# ArdBir_final.net
KiCad netlist of a schematic drawn in EAGLE
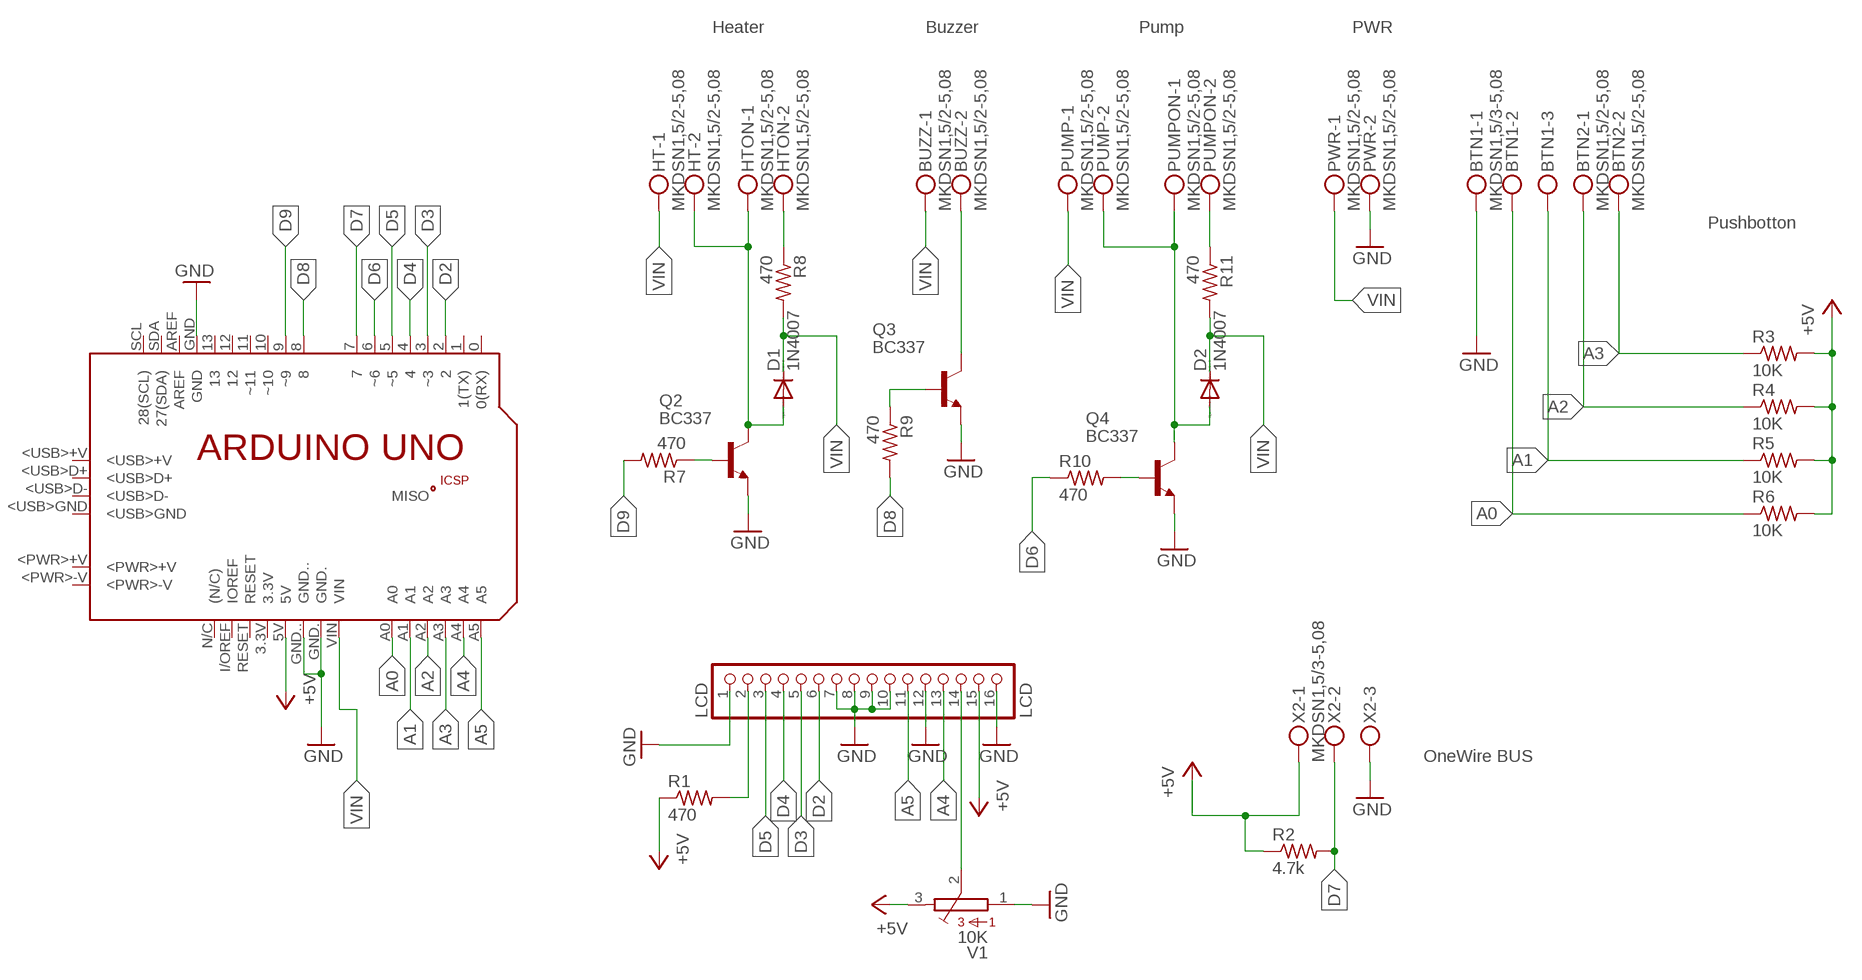
[diagram p0: schematic, sheet 1]

(export (version "E")
  (design (tool "Eeschema 10.0.6"))
  (components
    (comp (ref "BTN1")
      (value "MKDSN1,5/3-5,08")
      (footprint "eagle-import:MKDSN1,5_3-5,08")
      (fields (field (name "OC_NEWARK") "unknown"))
      (libsource (lib "eagle-import") (part "MKDSN1,5/3-5,08"))
    )
    (comp (ref "BTN2")
      (value "MKDSN1,5/2-5,08")
      (footprint "eagle-import:MKDSN1,5_2-5,08")
      (fields (field (name "OC_NEWARK") "unknown"))
      (libsource (lib "eagle-import") (part "MKDSN1,5/2-5,08"))
    )
    (comp (ref "BUZZ")
      (value "MKDSN1,5/2-5,08")
      (footprint "eagle-import:MKDSN1,5_2-5,08")
      (fields (field (name "OC_NEWARK") "unknown"))
      (libsource (lib "eagle-import") (part "MKDSN1,5/2-5,08"))
    )
    (comp (ref "D1")
      (value "1N4007")
      (footprint "eagle-import:DO41-10")
      (libsource (lib "eagle-import") (part "1N4004"))
    )
    (comp (ref "D2")
      (value "1N4007")
      (footprint "eagle-import:DO41-10")
      (libsource (lib "eagle-import") (part "1N4004"))
    )
    (comp (ref "HT")
      (value "MKDSN1,5/2-5,08")
      (footprint "eagle-import:MKDSN1,5_2-5,08")
      (fields (field (name "OC_NEWARK") "unknown"))
      (libsource (lib "eagle-import") (part "MKDSN1,5/2-5,08"))
    )
    (comp (ref "HTON")
      (value "MKDSN1,5/2-5,08")
      (footprint "eagle-import:MKDSN1,5_2-5,08")
      (fields (field (name "OC_NEWARK") "unknown"))
      (libsource (lib "eagle-import") (part "MKDSN1,5/2-5,08"))
    )
    (comp (ref "LCD")
      (value "LCD")
      (footprint "eagle-import:1X16")
      (libsource (lib "eagle-import") (part "PINHD-1X16"))
    )
    (comp (ref "PCB1")
      (value "ARDUINO_UNO")
      (footprint "eagle-import:ARDUINO_UNO")
      (libsource (lib "eagle-import") (part "ARDUINO_UNO"))
    )
    (comp (ref "PUMP")
      (value "MKDSN1,5/2-5,08")
      (footprint "eagle-import:MKDSN1,5_2-5,08")
      (fields (field (name "OC_NEWARK") "unknown"))
      (libsource (lib "eagle-import") (part "MKDSN1,5/2-5,08"))
    )
    (comp (ref "PUMPON")
      (value "MKDSN1,5/2-5,08")
      (footprint "eagle-import:MKDSN1,5_2-5,08")
      (fields (field (name "OC_NEWARK") "unknown"))
      (libsource (lib "eagle-import") (part "MKDSN1,5/2-5,08"))
    )
    (comp (ref "PWR")
      (value "MKDSN1,5/2-5,08")
      (footprint "eagle-import:MKDSN1,5_2-5,08")
      (fields (field (name "OC_NEWARK") "unknown"))
      (libsource (lib "eagle-import") (part "MKDSN1,5/2-5,08"))
    )
    (comp (ref "Q2")
      (value "BC337")
      (footprint "eagle-import:TO92")
      (libsource (lib "eagle-import") (part "BC337"))
    )
    (comp (ref "Q3")
      (value "BC337")
      (footprint "eagle-import:TO92")
      (libsource (lib "eagle-import") (part "BC337"))
    )
    (comp (ref "Q4")
      (value "BC337")
      (footprint "eagle-import:TO92")
      (libsource (lib "eagle-import") (part "BC337"))
    )
    (comp (ref "R1")
      (value "470")
      (footprint "eagle-import:0207_10")
      (libsource (lib "eagle-import") (part "R-US_0207/10"))
    )
    (comp (ref "R2")
      (value "4.7k")
      (footprint "eagle-import:0207_10")
      (libsource (lib "eagle-import") (part "R-US_0207/10"))
    )
    (comp (ref "R3")
      (value "10K")
      (footprint "eagle-import:0207_10")
      (libsource (lib "eagle-import") (part "R-US_0207/10"))
    )
    (comp (ref "R4")
      (value "10K")
      (footprint "eagle-import:0207_10")
      (libsource (lib "eagle-import") (part "R-US_0207/10"))
    )
    (comp (ref "R5")
      (value "10K")
      (footprint "eagle-import:0207_10")
      (libsource (lib "eagle-import") (part "R-US_0207/10"))
    )
    (comp (ref "R6")
      (value "10K")
      (footprint "eagle-import:0207_10")
      (libsource (lib "eagle-import") (part "R-US_0207/10"))
    )
    (comp (ref "R7")
      (value "470")
      (footprint "eagle-import:0207_10")
      (libsource (lib "eagle-import") (part "R-US_0207/10"))
    )
    (comp (ref "R8")
      (value "470")
      (footprint "eagle-import:0207_10")
      (libsource (lib "eagle-import") (part "R-US_0207/10"))
    )
    (comp (ref "R9")
      (value "470")
      (footprint "eagle-import:0207_10")
      (libsource (lib "eagle-import") (part "R-US_0207/10"))
    )
    (comp (ref "R10")
      (value "470")
      (footprint "eagle-import:0207_10")
      (libsource (lib "eagle-import") (part "R-US_0207/10"))
    )
    (comp (ref "R11")
      (value "470")
      (footprint "eagle-import:0207_10")
      (libsource (lib "eagle-import") (part "R-US_0207/10"))
    )
    (comp (ref "V1")
      (value "10K")
      (footprint "eagle-import:CA9V")
      (libsource (lib "eagle-import") (part "CA9V"))
    )
    (comp (ref "X2")
      (value "MKDSN1,5/3-5,08")
      (footprint "eagle-import:MKDSN1,5_3-5,08")
      (fields (field (name "OC_NEWARK") "unknown"))
      (libsource (lib "eagle-import") (part "MKDSN1,5/3-5,08"))
    )
  )
  (nets
    (net (code "1") (name "+5V") (class "Default")
      (node (ref "LCD") (pin "15") (pinfunction "15_15") (pintype "passive"))
      (node (ref "PCB1") (pin "5V") (pinfunction "5V_5V") (pintype "bidirectional"))
      (node (ref "R1") (pin "1") (pinfunction "1_1") (pintype "passive"))
      (node (ref "R2") (pin "1") (pinfunction "1_1") (pintype "passive"))
      (node (ref "R3") (pin "2") (pinfunction "2_2") (pintype "passive"))
      (node (ref "R4") (pin "2") (pinfunction "2_2") (pintype "passive"))
      (node (ref "R5") (pin "2") (pinfunction "2_2") (pintype "passive"))
      (node (ref "R6") (pin "2") (pinfunction "2_2") (pintype "passive"))
      (node (ref "V1") (pin "3") (pinfunction "3_3") (pintype "passive"))
      (node (ref "X2") (pin "1") (pinfunction "KL_1") (pintype "passive"))
    )
    (net (code "2") (name "A0") (class "Default")
      (node (ref "BTN1") (pin "2") (pinfunction "KL_2") (pintype "passive"))
      (node (ref "PCB1") (pin "A0") (pinfunction "A0_A0") (pintype "bidirectional"))
      (node (ref "R6") (pin "1") (pinfunction "1_1") (pintype "passive"))
    )
    (net (code "3") (name "A1") (class "Default")
      (node (ref "BTN1") (pin "3") (pinfunction "KL_3") (pintype "passive"))
      (node (ref "PCB1") (pin "A1") (pinfunction "A1_A1") (pintype "bidirectional"))
      (node (ref "R5") (pin "1") (pinfunction "1_1") (pintype "passive"))
    )
    (net (code "4") (name "A2") (class "Default")
      (node (ref "BTN2") (pin "1") (pinfunction "KL_1") (pintype "passive"))
      (node (ref "PCB1") (pin "A2") (pinfunction "A2_A2") (pintype "bidirectional"))
      (node (ref "R4") (pin "1") (pinfunction "1_1") (pintype "passive"))
    )
    (net (code "5") (name "A3") (class "Default")
      (node (ref "BTN2") (pin "2") (pinfunction "KL_2") (pintype "passive"))
      (node (ref "PCB1") (pin "A3") (pinfunction "A3_A3") (pintype "bidirectional"))
      (node (ref "R3") (pin "1") (pinfunction "1_1") (pintype "passive"))
    )
    (net (code "6") (name "A4") (class "Default")
      (node (ref "LCD") (pin "13") (pinfunction "13_13") (pintype "passive"))
      (node (ref "PCB1") (pin "A4") (pinfunction "A4_A4") (pintype "bidirectional"))
    )
    (net (code "7") (name "A5") (class "Default")
      (node (ref "LCD") (pin "11") (pinfunction "11_11") (pintype "passive"))
      (node (ref "PCB1") (pin "A5") (pinfunction "A5_A5") (pintype "bidirectional"))
    )
    (net (code "8") (name "D2") (class "Default")
      (node (ref "LCD") (pin "6") (pinfunction "6_6") (pintype "passive"))
      (node (ref "PCB1") (pin "2") (pinfunction "2_2") (pintype "bidirectional"))
    )
    (net (code "9") (name "D3") (class "Default")
      (node (ref "LCD") (pin "5") (pinfunction "5_5") (pintype "passive"))
      (node (ref "PCB1") (pin "3") (pinfunction "~{3}_3") (pintype "bidirectional"))
    )
    (net (code "10") (name "D4") (class "Default")
      (node (ref "LCD") (pin "4") (pinfunction "4_4") (pintype "passive"))
      (node (ref "PCB1") (pin "4") (pinfunction "4_4") (pintype "bidirectional"))
    )
    (net (code "11") (name "D5") (class "Default")
      (node (ref "LCD") (pin "3") (pinfunction "3_3") (pintype "passive"))
      (node (ref "PCB1") (pin "5") (pinfunction "~{5}_5") (pintype "bidirectional"))
    )
    (net (code "12") (name "D6") (class "Default")
      (node (ref "PCB1") (pin "6") (pinfunction "~{6}_6") (pintype "bidirectional"))
      (node (ref "R10") (pin "1") (pinfunction "1_1") (pintype "passive"))
    )
    (net (code "13") (name "D7") (class "Default")
      (node (ref "PCB1") (pin "7") (pinfunction "7_7") (pintype "bidirectional"))
      (node (ref "R2") (pin "2") (pinfunction "2_2") (pintype "passive"))
      (node (ref "X2") (pin "2") (pinfunction "KL_2") (pintype "passive"))
    )
    (net (code "14") (name "D8") (class "Default")
      (node (ref "PCB1") (pin "8") (pinfunction "8_8") (pintype "bidirectional"))
      (node (ref "R9") (pin "2") (pinfunction "2_2") (pintype "passive"))
    )
    (net (code "15") (name "D9") (class "Default")
      (node (ref "PCB1") (pin "9") (pinfunction "~{9}_9") (pintype "bidirectional"))
      (node (ref "R7") (pin "2") (pinfunction "2_2") (pintype "passive"))
    )
    (net (code "16") (name "GND") (class "Default")
      (node (ref "BTN1") (pin "1") (pinfunction "KL_1") (pintype "passive"))
      (node (ref "LCD") (pin "1") (pinfunction "1_1") (pintype "passive"))
      (node (ref "LCD") (pin "10") (pinfunction "10_10") (pintype "passive"))
      (node (ref "LCD") (pin "12") (pinfunction "12_12") (pintype "passive"))
      (node (ref "LCD") (pin "16") (pinfunction "16_16") (pintype "passive"))
      (node (ref "LCD") (pin "7") (pinfunction "7_7") (pintype "passive"))
      (node (ref "LCD") (pin "8") (pinfunction "8_8") (pintype "passive"))
      (node (ref "LCD") (pin "9") (pinfunction "9_9") (pintype "passive"))
      (node (ref "PCB1") (pin "GND") (pinfunction "GND_GND") (pintype "bidirectional"))
      (node (ref "PCB1") (pin "GND.") (pinfunction "GND._GND.") (pintype "bidirectional"))
      (node (ref "PCB1") (pin "GND..") (pinfunction "GND.._GND..") (pintype "bidirectional"))
      (node (ref "PWR") (pin "2") (pinfunction "KL_2") (pintype "passive"))
      (node (ref "Q2") (pin "1") (pinfunction "E_1") (pintype "passive"))
      (node (ref "Q3") (pin "1") (pinfunction "E_1") (pintype "passive"))
      (node (ref "Q4") (pin "1") (pinfunction "E_1") (pintype "passive"))
      (node (ref "V1") (pin "1") (pinfunction "1_1") (pintype "passive"))
      (node (ref "X2") (pin "3") (pinfunction "KL_3") (pintype "passive"))
    )
    (net (code "17") (name "Net-(BUZZB-KL)") (class "Default")
      (node (ref "BUZZ") (pin "2") (pinfunction "KL_2") (pintype "passive"))
      (node (ref "Q3") (pin "3") (pinfunction "C_3") (pintype "passive"))
    )
    (net (code "18") (name "Net-(HTB-KL)") (class "Default")
      (node (ref "D1") (pin "A") (pinfunction "A_A") (pintype "passive"))
      (node (ref "HT") (pin "2") (pinfunction "KL_2") (pintype "passive"))
      (node (ref "HTON") (pin "1") (pinfunction "KL_1") (pintype "passive"))
      (node (ref "Q2") (pin "3") (pinfunction "C_3") (pintype "passive"))
    )
    (net (code "19") (name "Net-(HTONB-KL)") (class "Default")
      (node (ref "HTON") (pin "2") (pinfunction "KL_2") (pintype "passive"))
      (node (ref "R8") (pin "1") (pinfunction "1_1") (pintype "passive"))
    )
    (net (code "20") (name "Net-(LCD-Pad2)") (class "Default")
      (node (ref "LCD") (pin "2") (pinfunction "2_2") (pintype "passive"))
      (node (ref "R1") (pin "2") (pinfunction "2_2") (pintype "passive"))
    )
    (net (code "21") (name "Net-(LCD-Pad14)") (class "Default")
      (node (ref "LCD") (pin "14") (pinfunction "14_14") (pintype "passive"))
      (node (ref "V1") (pin "2") (pinfunction "2_2") (pintype "passive"))
    )
    (net (code "22") (name "Net-(PUMPB-KL)") (class "Default")
      (node (ref "D2") (pin "A") (pinfunction "A_A") (pintype "passive"))
      (node (ref "PUMP") (pin "2") (pinfunction "KL_2") (pintype "passive"))
      (node (ref "PUMPON") (pin "1") (pinfunction "KL_1") (pintype "passive"))
      (node (ref "Q4") (pin "3") (pinfunction "C_3") (pintype "passive"))
    )
    (net (code "23") (name "Net-(PUMPONB-KL)") (class "Default")
      (node (ref "PUMPON") (pin "2") (pinfunction "KL_2") (pintype "passive"))
      (node (ref "R11") (pin "1") (pinfunction "1_1") (pintype "passive"))
    )
    (net (code "24") (name "Net-(Q2-B)") (class "Default")
      (node (ref "Q2") (pin "2") (pinfunction "B_2") (pintype "passive"))
      (node (ref "R7") (pin "1") (pinfunction "1_1") (pintype "passive"))
    )
    (net (code "25") (name "Net-(Q3-B)") (class "Default")
      (node (ref "Q3") (pin "2") (pinfunction "B_2") (pintype "passive"))
      (node (ref "R9") (pin "1") (pinfunction "1_1") (pintype "passive"))
    )
    (net (code "26") (name "Net-(Q4-B)") (class "Default")
      (node (ref "Q4") (pin "2") (pinfunction "B_2") (pintype "passive"))
      (node (ref "R10") (pin "2") (pinfunction "2_2") (pintype "passive"))
    )
    (net (code "27") (name "VIN") (class "Default")
      (node (ref "BUZZ") (pin "1") (pinfunction "KL_1") (pintype "passive"))
      (node (ref "D1") (pin "C") (pinfunction "C_C") (pintype "passive"))
      (node (ref "D2") (pin "C") (pinfunction "C_C") (pintype "passive"))
      (node (ref "HT") (pin "1") (pinfunction "KL_1") (pintype "passive"))
      (node (ref "PCB1") (pin "VIN") (pinfunction "VIN_VIN") (pintype "bidirectional"))
      (node (ref "PUMP") (pin "1") (pinfunction "KL_1") (pintype "passive"))
      (node (ref "PWR") (pin "1") (pinfunction "KL_1") (pintype "passive"))
      (node (ref "R11") (pin "2") (pinfunction "2_2") (pintype "passive"))
      (node (ref "R8") (pin "2") (pinfunction "2_2") (pintype "passive"))
    )
    (net (code "28") (name "unconnected-(PCB1-(N{slash}C)-PadN{slash}C)") (class "Default")
      (node (ref "PCB1") (pin "N/C") (pinfunction "(N/C)_N/C") (pintype "bidirectional"))
    )
    (net (code "29") (name "unconnected-(PCB1-0(RX)-Pad0)") (class "Default")
      (node (ref "PCB1") (pin "0") (pinfunction "0(RX)_0") (pintype "bidirectional"))
    )
    (net (code "30") (name "unconnected-(PCB1-1(TX)-Pad1)") (class "Default")
      (node (ref "PCB1") (pin "1") (pinfunction "1(TX)_1") (pintype "bidirectional"))
    )
    (net (code "31") (name "unconnected-(PCB1-27(SDA)-PadSDA)") (class "Default")
      (node (ref "PCB1") (pin "SDA") (pinfunction "27(SDA)_SDA") (pintype "bidirectional"))
    )
    (net (code "32") (name "unconnected-(PCB1-28(SCL)-PadSCL)") (class "Default")
      (node (ref "PCB1") (pin "SCL") (pinfunction "28(SCL)_SCL") (pintype "bidirectional"))
    )
    (net (code "33") (name "unconnected-(PCB1-IOREF-PadI{slash}OREF)") (class "Default")
      (node (ref "PCB1") (pin "I/OREF") (pinfunction "IOREF_I/OREF") (pintype "bidirectional"))
    )
    (net (code "34") (name "unconnected-(PCB1-MISO-Pad01)") (class "Default")
      (node (ref "PCB1") (pin "01") (pinfunction "MISO_01") (pintype "bidirectional"))
    )
    (net (code "35") (name "unconnected-(PCB1-Pad+5V)") (class "Default")
      (node (ref "PCB1") (pin "+5V") (pinfunction "+5V_+5V") (pintype "bidirectional"))
    )
    (net (code "36") (name "unconnected-(PCB1-Pad3.3V)") (class "Default")
      (node (ref "PCB1") (pin "3.3V") (pinfunction "3.3V_3.3V") (pintype "bidirectional"))
    )
    (net (code "37") (name "unconnected-(PCB1-Pad12)") (class "Default")
      (node (ref "PCB1") (pin "12") (pinfunction "12_12") (pintype "bidirectional"))
    )
    (net (code "38") (name "unconnected-(PCB1-Pad13)") (class "Default")
      (node (ref "PCB1") (pin "13") (pinfunction "13_13") (pintype "bidirectional"))
    )
    (net (code "39") (name "unconnected-(PCB1-Pad<PWR>+V)") (class "Default")
      (node (ref "PCB1") (pin "<PWR>+V") (pinfunction "<PWR>+V_<PWR>+V") (pintype "bidirectional"))
    )
    (net (code "40") (name "unconnected-(PCB1-Pad<PWR>-V)") (class "Default")
      (node (ref "PCB1") (pin "<PWR>-V") (pinfunction "<PWR>-V_<PWR>-V") (pintype "bidirectional"))
    )
    (net (code "41") (name "unconnected-(PCB1-Pad<USB>+V)") (class "Default")
      (node (ref "PCB1") (pin "<USB>+V") (pinfunction "<USB>+V_<USB>+V") (pintype "bidirectional"))
    )
    (net (code "42") (name "unconnected-(PCB1-Pad<USB>D+)") (class "Default")
      (node (ref "PCB1") (pin "<USB>D+") (pinfunction "<USB>D+_<USB>D+") (pintype "bidirectional"))
    )
    (net (code "43") (name "unconnected-(PCB1-Pad<USB>D-)") (class "Default")
      (node (ref "PCB1") (pin "<USB>D-") (pinfunction "<USB>D-_<USB>D-") (pintype "bidirectional"))
    )
    (net (code "44") (name "unconnected-(PCB1-Pad<USB>GND)") (class "Default")
      (node (ref "PCB1") (pin "<USB>GND") (pinfunction "<USB>GND_<USB>GND") (pintype "bidirectional"))
    )
    (net (code "45") (name "unconnected-(PCB1-PadAREF)") (class "Default")
      (node (ref "PCB1") (pin "AREF") (pinfunction "AREF_AREF") (pintype "bidirectional"))
    )
    (net (code "46") (name "unconnected-(PCB1-PadGND_)") (class "Default")
      (node (ref "PCB1") (pin "GND_") (pinfunction "GND__GND_") (pintype "bidirectional"))
    )
    (net (code "47") (name "unconnected-(PCB1-PadMOSI)") (class "Default")
      (node (ref "PCB1") (pin "MOSI") (pinfunction "MOSI_MOSI") (pintype "bidirectional"))
    )
    (net (code "48") (name "unconnected-(PCB1-PadRESET)") (class "Default")
      (node (ref "PCB1") (pin "RESET") (pinfunction "RESET_RESET") (pintype "bidirectional"))
    )
    (net (code "49") (name "unconnected-(PCB1-PadRESET.)") (class "Default")
      (node (ref "PCB1") (pin "RESET.") (pinfunction "RESET._RESET.") (pintype "bidirectional"))
    )
    (net (code "50") (name "unconnected-(PCB1-PadSCK)") (class "Default")
      (node (ref "PCB1") (pin "SCK") (pinfunction "SCK_SCK") (pintype "bidirectional"))
    )
    (net (code "51") (name "unconnected-(PCB1-~{10}-Pad10)") (class "Default")
      (node (ref "PCB1") (pin "10") (pinfunction "~{10}_10") (pintype "bidirectional"))
    )
    (net (code "52") (name "unconnected-(PCB1-~{11}-Pad11)") (class "Default")
      (node (ref "PCB1") (pin "11") (pinfunction "~{11}_11") (pintype "bidirectional"))
    )
  )
)
